# CENTRALLEDS.net
KiCad netlist of a schematic drawn in Altium Designer
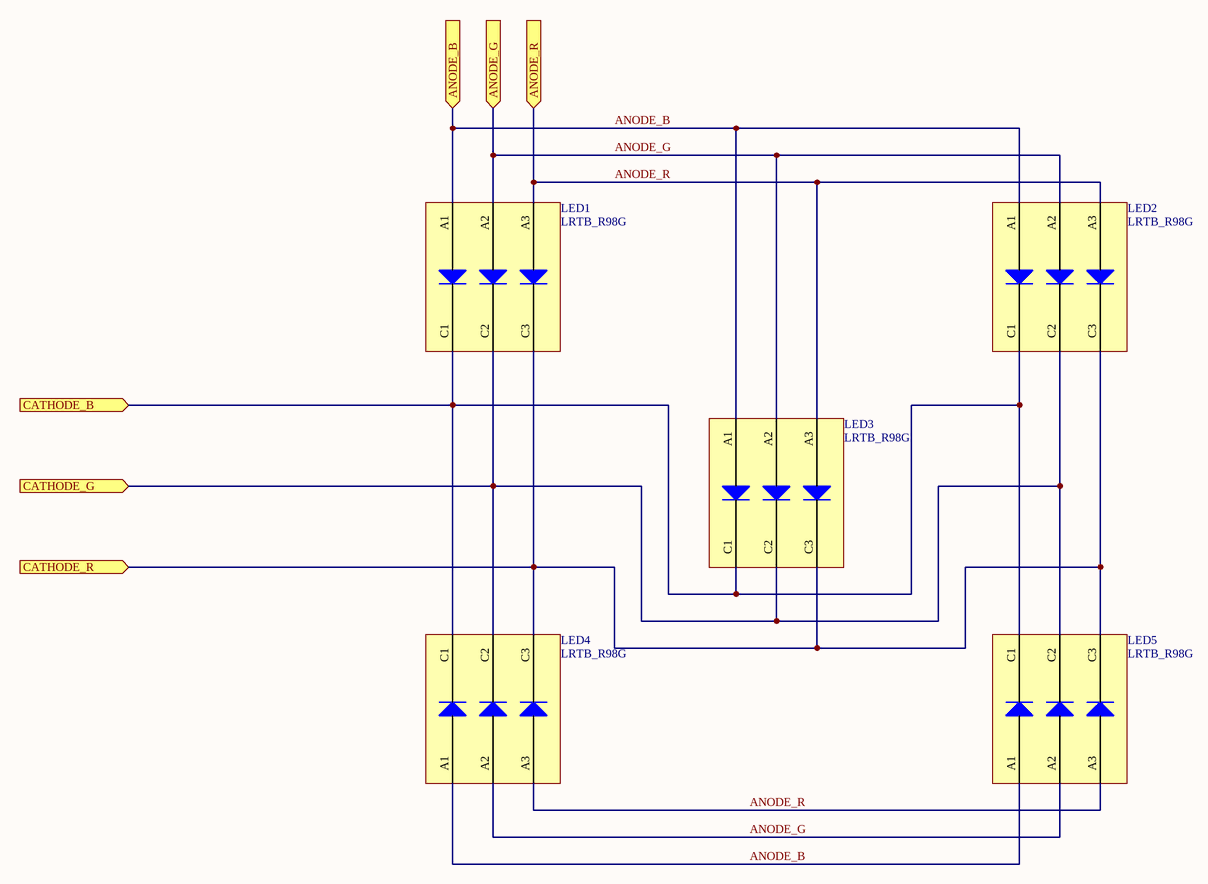
[diagram p0: CENTRALLEDS.SchDoc]

(export (version "E")
  (design (tool "Eeschema 10.0.6"))
  (components
    (comp (ref "LED1")
      (value "LRTB_R98G")
      (footprint "LRTB_R98G")
      (description "IC RGB LED OSRAM")
      (fields (field (name "MANUFACTURER") "OSRAM"))
      (libsource (lib "") (part "LRTB_R98G_1"))
    )
    (comp (ref "LED2")
      (value "LRTB_R98G")
      (footprint "LRTB_R98G")
      (description "IC RGB LED OSRAM")
      (fields (field (name "MANUFACTURER") "OSRAM"))
      (libsource (lib "") (part "LRTB_R98G_1"))
    )
    (comp (ref "LED3")
      (value "LRTB_R98G")
      (footprint "LRTB_R98G")
      (description "IC RGB LED OSRAM")
      (fields (field (name "MANUFACTURER") "OSRAM"))
      (libsource (lib "") (part "LRTB_R98G_1"))
    )
    (comp (ref "LED4")
      (value "LRTB_R98G")
      (footprint "LRTB_R98G")
      (description "IC RGB LED OSRAM")
      (fields (field (name "MANUFACTURER") "OSRAM"))
      (libsource (lib "SmartHalo_Symbols") (part "LRTB_R98G"))
    )
    (comp (ref "LED5")
      (value "LRTB_R98G")
      (footprint "LRTB_R98G")
      (description "IC RGB LED OSRAM")
      (fields (field (name "MANUFACTURER") "OSRAM"))
      (libsource (lib "SmartHalo_Symbols") (part "LRTB_R98G"))
    )
  )
  (nets
    (net (code "1") (name "/ANODE_B") (class "Default")
      (node (ref "LED1") (pin "A1") (pinfunction "Anode_Blue_A1") (pintype "passive"))
      (node (ref "LED2") (pin "A1") (pinfunction "Anode_Blue_A1") (pintype "passive"))
      (node (ref "LED3") (pin "A1") (pinfunction "Anode_Blue_A1") (pintype "passive"))
      (node (ref "LED4") (pin "A1") (pinfunction "Anode_Blue_A1") (pintype "passive"))
      (node (ref "LED5") (pin "A1") (pinfunction "Anode_Blue_A1") (pintype "passive"))
    )
    (net (code "2") (name "/ANODE_G") (class "Default")
      (node (ref "LED1") (pin "A2") (pinfunction "Anode_Green_A2") (pintype "passive"))
      (node (ref "LED2") (pin "A2") (pinfunction "Anode_Green_A2") (pintype "passive"))
      (node (ref "LED3") (pin "A2") (pinfunction "Anode_Green_A2") (pintype "passive"))
      (node (ref "LED4") (pin "A2") (pinfunction "Anode_Green_A2") (pintype "passive"))
      (node (ref "LED5") (pin "A2") (pinfunction "Anode_Green_A2") (pintype "passive"))
    )
    (net (code "3") (name "/ANODE_R") (class "Default")
      (node (ref "LED1") (pin "A3") (pinfunction "Anode_Red_A3") (pintype "passive"))
      (node (ref "LED2") (pin "A3") (pinfunction "Anode_Red_A3") (pintype "passive"))
      (node (ref "LED3") (pin "A3") (pinfunction "Anode_Red_A3") (pintype "passive"))
      (node (ref "LED4") (pin "A3") (pinfunction "Anode_Red_A3") (pintype "passive"))
      (node (ref "LED5") (pin "A3") (pinfunction "Anode_Red_A3") (pintype "passive"))
    )
    (net (code "4") (name "/CATHODE_B") (class "Default")
      (node (ref "LED1") (pin "C1") (pinfunction "Cathode_Blue_C1") (pintype "passive"))
      (node (ref "LED2") (pin "C1") (pinfunction "Cathode_Blue_C1") (pintype "passive"))
      (node (ref "LED3") (pin "C1") (pinfunction "Cathode_Blue_C1") (pintype "passive"))
      (node (ref "LED4") (pin "C1") (pinfunction "Cathode_Blue_C1") (pintype "passive"))
      (node (ref "LED5") (pin "C1") (pinfunction "Cathode_Blue_C1") (pintype "passive"))
    )
    (net (code "5") (name "/CATHODE_G") (class "Default")
      (node (ref "LED1") (pin "C2") (pinfunction "Cathode_Green_C2") (pintype "passive"))
      (node (ref "LED2") (pin "C2") (pinfunction "Cathode_Green_C2") (pintype "passive"))
      (node (ref "LED3") (pin "C2") (pinfunction "Cathode_Green_C2") (pintype "passive"))
      (node (ref "LED4") (pin "C2") (pinfunction "Cathode_Green_C2") (pintype "passive"))
      (node (ref "LED5") (pin "C2") (pinfunction "Cathode_Green_C2") (pintype "passive"))
    )
    (net (code "6") (name "/CATHODE_R") (class "Default")
      (node (ref "LED1") (pin "C3") (pinfunction "Cathode_Red_C3") (pintype "passive"))
      (node (ref "LED2") (pin "C3") (pinfunction "Cathode_Red_C3") (pintype "passive"))
      (node (ref "LED3") (pin "C3") (pinfunction "Cathode_Red_C3") (pintype "passive"))
      (node (ref "LED4") (pin "C3") (pinfunction "Cathode_Red_C3") (pintype "passive"))
      (node (ref "LED5") (pin "C3") (pinfunction "Cathode_Red_C3") (pintype "passive"))
    )
  )
)
